# TEMP.net
KiCad netlist of a schematic drawn in Altium Designer
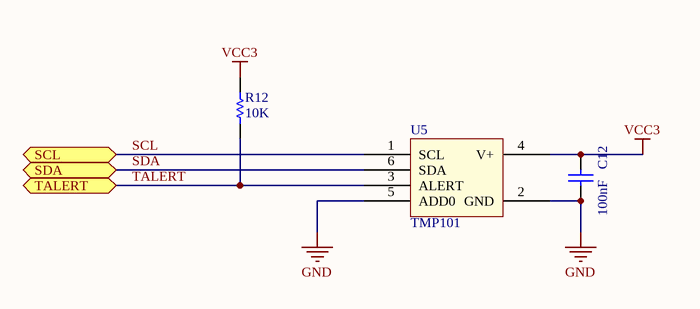
[diagram p0: TEMP.SchDoc]

(export (version "E")
  (design (tool "Eeschema 10.0.6"))
  (components
    (comp (ref "C12")
      (value "100nF")
      (footprint "RESC2012L")
      (description "Capacitor (Semiconductor SIM Model)")
      (fields (field (name "Comment") "Cap Semi") (field (name "PUBLISHER") "Altium Limited"))
      (libsource (lib "Miscellaneous Devices") (part "Cap Semi"))
    )
    (comp (ref "R12")
      (value "10K")
      (footprint "RES0805")
      (description "Semiconductor Resistor")
      (fields (field (name "Comment") "Res Semi") (field (name "PUBLISHER") "Altium Limited"))
      (libsource (lib "Miscellaneous Devices") (part "Res Semi"))
    )
    (comp (ref "U5")
      (value "TMP101")
      (footprint "SOT23-6_L")
      (description "I2C Temperature Sensor")
      (libsource (lib "Library") (part "TMP101"))
    )
  )
  (nets
    (net (code "1") (name "/SCL") (class "Default")
      (node (ref "U5") (pin "1") (pinfunction "SCL_1") (pintype "passive"))
    )
    (net (code "2") (name "/SDA") (class "Default")
      (node (ref "U5") (pin "6") (pinfunction "SDA_6") (pintype "passive"))
    )
    (net (code "3") (name "/TALERT") (class "Default")
      (node (ref "R12") (pin "1") (pinfunction "1_1") (pintype "passive"))
      (node (ref "U5") (pin "3") (pinfunction "ALERT_3") (pintype "passive"))
    )
    (net (code "4") (name "GND") (class "Default")
      (node (ref "C12") (pin "1") (pinfunction "1_1") (pintype "passive"))
      (node (ref "U5") (pin "2") (pinfunction "GND_2") (pintype "passive"))
      (node (ref "U5") (pin "5") (pinfunction "ADD0_5") (pintype "passive"))
    )
    (net (code "5") (name "VCC3") (class "Default")
      (node (ref "C12") (pin "2") (pinfunction "2_2") (pintype "passive"))
      (node (ref "R12") (pin "2") (pinfunction "2_2") (pintype "passive"))
      (node (ref "U5") (pin "4") (pinfunction "V+_4") (pintype "passive"))
    )
  )
)
